# 1_LPC1850__P0-P4.net
KiCad netlist of a schematic drawn in Altium Designer
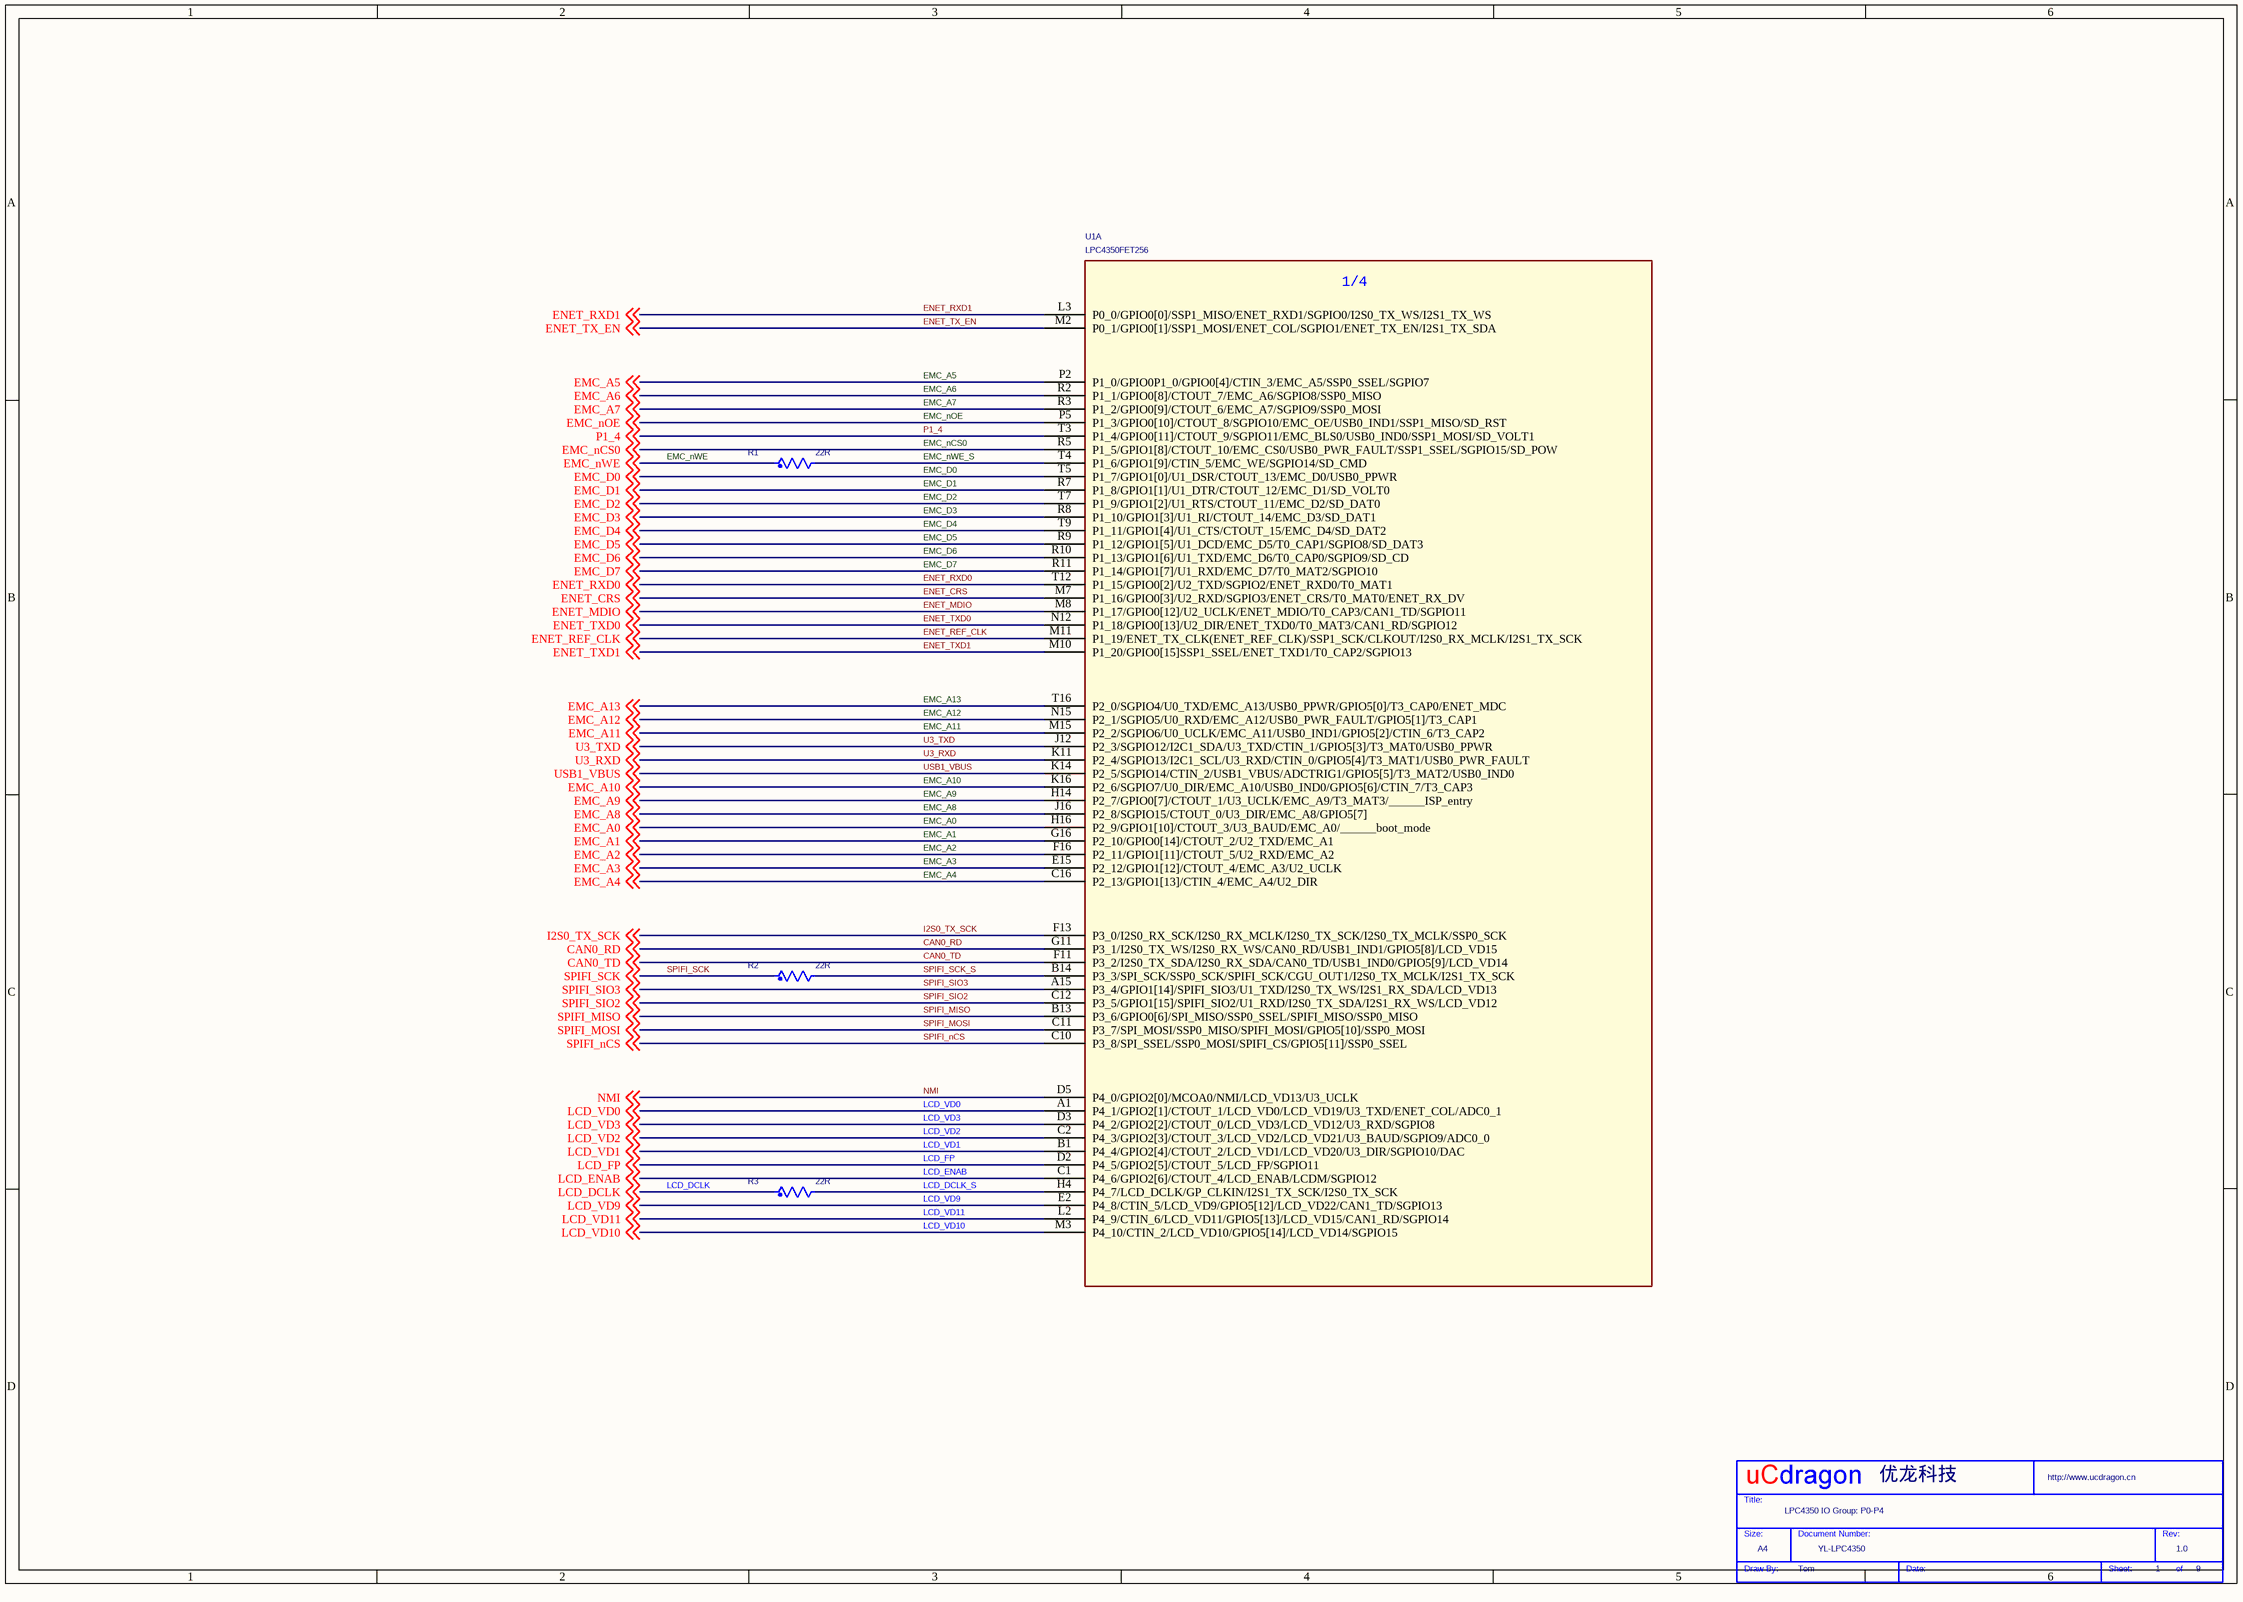
[diagram p0: 1) LPC1850_ P0-P4.SchDoc]

(export (version "E")
  (design (tool "Eeschema 10.0.6"))
  (components
    (comp (ref "*")
      (value "My Title 0")
      (fields
        (field (name "COMPANY") "优龙科技")
        (field (name "DRAWING") "Tom")
        (field (name "WEBSITE") "http://www.ucdragon.cn")
        (field (name "DOC") "YL-LPC4350")
        (field (name "REVCODE") "1.0")
        (field (name "TITLE") "LPC4350 IO Group: P0-P4")
        (field (name "PAGE SIZE") "A4")
        (field (name "PAGE NUMBER") "1")
        (field (name "PAGE COUNT") "9")
      )
      (libsource (lib "*") (part "My Title 0"))
    )
    (comp (ref "R1") (value "22R") (libsource (lib "*") (part "R_Generic_Dup2")))
    (comp (ref "R2") (value "22R") (libsource (lib "*") (part "R_Generic_Dup2")))
    (comp (ref "R3") (value "22R") (libsource (lib "*") (part "R_Generic_Dup2")))
    (comp (ref "U1")
      (value "LPC4350FET256")
      (footprint "LBGA256")
      (libsource (lib "*") (part "LPC4350FET256"))
    )
  )
  (nets
    (net (code "1") (name "/EMC_nWE_S") (class "Default")
      (node (ref "R1") (pin "2") (pinfunction "2_2") (pintype "passive"))
      (node (ref "U1") (pin "T4") (pinfunction "P1_6/GPIO1[9]/CTIN_5/EMC_WE/SGPIO14/SD_CMD_T4") (pintype "passive"))
    )
    (net (code "2") (name "/LCD_DCLK_S") (class "Default")
      (node (ref "R3") (pin "2") (pinfunction "2_2") (pintype "passive"))
      (node (ref "U1") (pin "H4") (pinfunction "P4_7/LCD_DCLK/GP_CLKIN/I2S1_TX_SCK/I2S0_TX_SCK_H4") (pintype "passive"))
    )
    (net (code "3") (name "/SPIFI_SCK_S") (class "Default")
      (node (ref "R2") (pin "2") (pinfunction "2_2") (pintype "passive"))
      (node (ref "U1") (pin "B14") (pinfunction "P3_3/SPI_SCK/SSP0_SCK/SPIFI_SCK/CGU_OUT1/I2S0_TX_MCLK/I2S1_TX_SCK_B14") (pintype "passive"))
    )
    (net (code "4") (name "CAN0_RD") (class "Default")
      (node (ref "U1") (pin "G11") (pinfunction "P3_1/I2S0_TX_WS/I2S0_RX_WS/CAN0_RD/USB1_IND1/GPIO5[8]/LCD_VD15_G11") (pintype "passive"))
    )
    (net (code "5") (name "CAN0_TD") (class "Default")
      (node (ref "U1") (pin "F11") (pinfunction "P3_2/I2S0_TX_SDA/I2S0_RX_SDA/CAN0_TD/USB1_IND0/GPIO5[9]/LCD_VD14_F11") (pintype "passive"))
    )
    (net (code "6") (name "EMC_A0") (class "Default")
      (node (ref "U1") (pin "H16") (pinfunction "P2_9/GPIO1[10]/CTOUT_3/U3_BAUD/EMC_A0/______boot_mode_H16") (pintype "passive"))
    )
    (net (code "7") (name "EMC_A1") (class "Default")
      (node (ref "U1") (pin "G16") (pinfunction "P2_10/GPIO0[14]/CTOUT_2/U2_TXD/EMC_A1_G16") (pintype "passive"))
    )
    (net (code "8") (name "EMC_A2") (class "Default")
      (node (ref "U1") (pin "F16") (pinfunction "P2_11/GPIO1[11]/CTOUT_5/U2_RXD/EMC_A2_F16") (pintype "passive"))
    )
    (net (code "9") (name "EMC_A3") (class "Default")
      (node (ref "U1") (pin "E15") (pinfunction "P2_12/GPIO1[12]/CTOUT_4/EMC_A3/U2_UCLK_E15") (pintype "passive"))
    )
    (net (code "10") (name "EMC_A4") (class "Default")
      (node (ref "U1") (pin "C16") (pinfunction "P2_13/GPIO1[13]/CTIN_4/EMC_A4/U2_DIR_C16") (pintype "passive"))
    )
    (net (code "11") (name "EMC_A5") (class "Default")
      (node (ref "U1") (pin "P2") (pinfunction "P1_0/GPIO0P1_0/GPIO0[4]/CTIN_3/EMC_A5/SSP0_SSEL/SGPIO7_P2") (pintype "passive"))
    )
    (net (code "12") (name "EMC_A6") (class "Default")
      (node (ref "U1") (pin "R2") (pinfunction "P1_1/GPIO0[8]/CTOUT_7/EMC_A6/SGPIO8/SSP0_MISO_R2") (pintype "passive"))
    )
    (net (code "13") (name "EMC_A7") (class "Default")
      (node (ref "U1") (pin "R3") (pinfunction "P1_2/GPIO0[9]/CTOUT_6/EMC_A7/SGPIO9/SSP0_MOSI_R3") (pintype "passive"))
    )
    (net (code "14") (name "EMC_A8") (class "Default")
      (node (ref "U1") (pin "J16") (pinfunction "P2_8/SGPIO15/CTOUT_0/U3_DIR/EMC_A8/GPIO5[7]_J16") (pintype "passive"))
    )
    (net (code "15") (name "EMC_A9") (class "Default")
      (node (ref "U1") (pin "H14") (pinfunction "P2_7/GPIO0[7]/CTOUT_1/U3_UCLK/EMC_A9/T3_MAT3/______ISP_entry_H14") (pintype "passive"))
    )
    (net (code "16") (name "EMC_A10") (class "Default")
      (node (ref "U1") (pin "K16") (pinfunction "P2_6/SGPIO7/U0_DIR/EMC_A10/USB0_IND0/GPIO5[6]/CTIN_7/T3_CAP3_K16") (pintype "passive"))
    )
    (net (code "17") (name "EMC_A11") (class "Default")
      (node (ref "U1") (pin "M15") (pinfunction "P2_2/SGPIO6/U0_UCLK/EMC_A11/USB0_IND1/GPIO5[2]/CTIN_6/T3_CAP2_M15") (pintype "passive"))
    )
    (net (code "18") (name "EMC_A12") (class "Default")
      (node (ref "U1") (pin "N15") (pinfunction "P2_1/SGPIO5/U0_RXD/EMC_A12/USB0_PWR_FAULT/GPIO5[1]/T3_CAP1_N15") (pintype "passive"))
    )
    (net (code "19") (name "EMC_A13") (class "Default")
      (node (ref "U1") (pin "T16") (pinfunction "P2_0/SGPIO4/U0_TXD/EMC_A13/USB0_PPWR/GPIO5[0]/T3_CAP0/ENET_MDC_T16") (pintype "passive"))
    )
    (net (code "20") (name "EMC_D0") (class "Default")
      (node (ref "U1") (pin "T5") (pinfunction "P1_7/GPIO1[0]/U1_DSR/CTOUT_13/EMC_D0/USB0_PPWR_T5") (pintype "passive"))
    )
    (net (code "21") (name "EMC_D1") (class "Default")
      (node (ref "U1") (pin "R7") (pinfunction "P1_8/GPIO1[1]/U1_DTR/CTOUT_12/EMC_D1/SD_VOLT0_R7") (pintype "passive"))
    )
    (net (code "22") (name "EMC_D2") (class "Default")
      (node (ref "U1") (pin "T7") (pinfunction "P1_9/GPIO1[2]/U1_RTS/CTOUT_11/EMC_D2/SD_DAT0_T7") (pintype "passive"))
    )
    (net (code "23") (name "EMC_D3") (class "Default")
      (node (ref "U1") (pin "R8") (pinfunction "P1_10/GPIO1[3]/U1_RI/CTOUT_14/EMC_D3/SD_DAT1_R8") (pintype "passive"))
    )
    (net (code "24") (name "EMC_D4") (class "Default")
      (node (ref "U1") (pin "T9") (pinfunction "P1_11/GPIO1[4]/U1_CTS/CTOUT_15/EMC_D4/SD_DAT2_T9") (pintype "passive"))
    )
    (net (code "25") (name "EMC_D5") (class "Default")
      (node (ref "U1") (pin "R9") (pinfunction "P1_12/GPIO1[5]/U1_DCD/EMC_D5/T0_CAP1/SGPIO8/SD_DAT3_R9") (pintype "passive"))
    )
    (net (code "26") (name "EMC_D6") (class "Default")
      (node (ref "U1") (pin "R10") (pinfunction "P1_13/GPIO1[6]/U1_TXD/EMC_D6/T0_CAP0/SGPIO9/SD_CD_R10") (pintype "passive"))
    )
    (net (code "27") (name "EMC_D7") (class "Default")
      (node (ref "U1") (pin "R11") (pinfunction "P1_14/GPIO1[7]/U1_RXD/EMC_D7/T0_MAT2/SGPIO10_R11") (pintype "passive"))
    )
    (net (code "28") (name "EMC_nCS0") (class "Default")
      (node (ref "U1") (pin "R5") (pinfunction "P1_5/GPIO1[8]/CTOUT_10/EMC_CS0/USB0_PWR_FAULT/SSP1_SSEL/SGPIO15/SD_POW_R5") (pintype "passive"))
    )
    (net (code "29") (name "EMC_nOE") (class "Default")
      (node (ref "U1") (pin "P5") (pinfunction "P1_3/GPIO0[10]/CTOUT_8/SGPIO10/EMC_OE/USB0_IND1/SSP1_MISO/SD_RST_P5") (pintype "passive"))
    )
    (net (code "30") (name "EMC_nWE") (class "Default")
      (node (ref "R1") (pin "1") (pinfunction "1_1") (pintype "passive"))
    )
    (net (code "31") (name "ENET_CRS") (class "Default")
      (node (ref "U1") (pin "M7") (pinfunction "P1_16/GPIO0[3]/U2_RXD/SGPIO3/ENET_CRS/T0_MAT0/ENET_RX_DV_M7") (pintype "passive"))
    )
    (net (code "32") (name "ENET_MDIO") (class "Default")
      (node (ref "U1") (pin "M8") (pinfunction "P1_17/GPIO0[12]/U2_UCLK/ENET_MDIO/T0_CAP3/CAN1_TD/SGPIO11_M8") (pintype "passive"))
    )
    (net (code "33") (name "ENET_REF_CLK") (class "Default")
      (node (ref "U1") (pin "M11") (pinfunction "P1_19/ENET_TX_CLK(ENET_REF_CLK)/SSP1_SCK/CLKOUT/I2S0_RX_MCLK/I2S1_TX_SCK_M11") (pintype "passive"))
    )
    (net (code "34") (name "ENET_RXD0") (class "Default")
      (node (ref "U1") (pin "T12") (pinfunction "P1_15/GPIO0[2]/U2_TXD/SGPIO2/ENET_RXD0/T0_MAT1_T12") (pintype "passive"))
    )
    (net (code "35") (name "ENET_RXD1") (class "Default")
      (node (ref "U1") (pin "L3") (pinfunction "P0_0/GPIO0[0]/SSP1_MISO/ENET_RXD1/SGPIO0/I2S0_TX_WS/I2S1_TX_WS_L3") (pintype "passive"))
    )
    (net (code "36") (name "ENET_TXD0") (class "Default")
      (node (ref "U1") (pin "N12") (pinfunction "P1_18/GPIO0[13]/U2_DIR/ENET_TXD0/T0_MAT3/CAN1_RD/SGPIO12_N12") (pintype "passive"))
    )
    (net (code "37") (name "ENET_TXD1") (class "Default")
      (node (ref "U1") (pin "M10") (pinfunction "P1_20/GPIO0[15]SSP1_SSEL/ENET_TXD1/T0_CAP2/SGPIO13_M10") (pintype "passive"))
    )
    (net (code "38") (name "ENET_TX_EN") (class "Default")
      (node (ref "U1") (pin "M2") (pinfunction "P0_1/GPIO0[1]/SSP1_MOSI/ENET_COL/SGPIO1/ENET_TX_EN/I2S1_TX_SDA_M2") (pintype "passive"))
    )
    (net (code "39") (name "I2S0_TX_SCK") (class "Default")
      (node (ref "U1") (pin "F13") (pinfunction "P3_0/I2S0_RX_SCK/I2S0_RX_MCLK/I2S0_TX_SCK/I2S0_TX_MCLK/SSP0_SCK_F13") (pintype "passive"))
    )
    (net (code "40") (name "LCD_DCLK") (class "Default")
      (node (ref "R3") (pin "1") (pinfunction "1_1") (pintype "passive"))
    )
    (net (code "41") (name "LCD_ENAB") (class "Default")
      (node (ref "U1") (pin "C1") (pinfunction "P4_6/GPIO2[6]/CTOUT_4/LCD_ENAB/LCDM/SGPIO12_C1") (pintype "passive"))
    )
    (net (code "42") (name "LCD_FP") (class "Default")
      (node (ref "U1") (pin "D2") (pinfunction "P4_5/GPIO2[5]/CTOUT_5/LCD_FP/SGPIO11_D2") (pintype "passive"))
    )
    (net (code "43") (name "LCD_VD0") (class "Default")
      (node (ref "U1") (pin "A1") (pinfunction "P4_1/GPIO2[1]/CTOUT_1/LCD_VD0/LCD_VD19/U3_TXD/ENET_COL/ADC0_1_A1") (pintype "passive"))
    )
    (net (code "44") (name "LCD_VD1") (class "Default")
      (node (ref "U1") (pin "B1") (pinfunction "P4_4/GPIO2[4]/CTOUT_2/LCD_VD1/LCD_VD20/U3_DIR/SGPIO10/DAC_B1") (pintype "passive"))
    )
    (net (code "45") (name "LCD_VD2") (class "Default")
      (node (ref "U1") (pin "C2") (pinfunction "P4_3/GPIO2[3]/CTOUT_3/LCD_VD2/LCD_VD21/U3_BAUD/SGPIO9/ADC0_0_C2") (pintype "passive"))
    )
    (net (code "46") (name "LCD_VD3") (class "Default")
      (node (ref "U1") (pin "D3") (pinfunction "P4_2/GPIO2[2]/CTOUT_0/LCD_VD3/LCD_VD12/U3_RXD/SGPIO8_D3") (pintype "passive"))
    )
    (net (code "47") (name "LCD_VD9") (class "Default")
      (node (ref "U1") (pin "E2") (pinfunction "P4_8/CTIN_5/LCD_VD9/GPIO5[12]/LCD_VD22/CAN1_TD/SGPIO13_E2") (pintype "passive"))
    )
    (net (code "48") (name "LCD_VD10") (class "Default")
      (node (ref "U1") (pin "M3") (pinfunction "P4_10/CTIN_2/LCD_VD10/GPIO5[14]/LCD_VD14/SGPIO15_M3") (pintype "passive"))
    )
    (net (code "49") (name "LCD_VD11") (class "Default")
      (node (ref "U1") (pin "L2") (pinfunction "P4_9/CTIN_6/LCD_VD11/GPIO5[13]/LCD_VD15/CAN1_RD/SGPIO14_L2") (pintype "passive"))
    )
    (net (code "50") (name "NMI") (class "Default")
      (node (ref "U1") (pin "D5") (pinfunction "P4_0/GPIO2[0]/MCOA0/NMI/LCD_VD13/U3_UCLK_D5") (pintype "passive"))
    )
    (net (code "51") (name "P1_4") (class "Default")
      (node (ref "U1") (pin "T3") (pinfunction "P1_4/GPIO0[11]/CTOUT_9/SGPIO11/EMC_BLS0/USB0_IND0/SSP1_MOSI/SD_VOLT1_T3") (pintype "passive"))
    )
    (net (code "52") (name "SPIFI_MISO") (class "Default")
      (node (ref "U1") (pin "B13") (pinfunction "P3_6/GPIO0[6]/SPI_MISO/SSP0_SSEL/SPIFI_MISO/SSP0_MISO_B13") (pintype "passive"))
    )
    (net (code "53") (name "SPIFI_MOSI") (class "Default")
      (node (ref "U1") (pin "C11") (pinfunction "P3_7/SPI_MOSI/SSP0_MISO/SPIFI_MOSI/GPIO5[10]/SSP0_MOSI_C11") (pintype "passive"))
    )
    (net (code "54") (name "SPIFI_SCK") (class "Default")
      (node (ref "R2") (pin "1") (pinfunction "1_1") (pintype "passive"))
    )
    (net (code "55") (name "SPIFI_SIO2") (class "Default")
      (node (ref "U1") (pin "C12") (pinfunction "P3_5/GPIO1[15]/SPIFI_SIO2/U1_RXD/I2S0_TX_SDA/I2S1_RX_WS/LCD_VD12_C12") (pintype "passive"))
    )
    (net (code "56") (name "SPIFI_SIO3") (class "Default")
      (node (ref "U1") (pin "A15") (pinfunction "P3_4/GPIO1[14]/SPIFI_SIO3/U1_TXD/I2S0_TX_WS/I2S1_RX_SDA/LCD_VD13_A15") (pintype "passive"))
    )
    (net (code "57") (name "SPIFI_nCS") (class "Default")
      (node (ref "U1") (pin "C10") (pinfunction "P3_8/SPI_SSEL/SSP0_MOSI/SPIFI_CS/GPIO5[11]/SSP0_SSEL_C10") (pintype "passive"))
    )
    (net (code "58") (name "U3_RXD") (class "Default")
      (node (ref "U1") (pin "K11") (pinfunction "P2_4/SGPIO13/I2C1_SCL/U3_RXD/CTIN_0/GPIO5[4]/T3_MAT1/USB0_PWR_FAULT_K11") (pintype "passive"))
    )
    (net (code "59") (name "U3_TXD") (class "Default")
      (node (ref "U1") (pin "J12") (pinfunction "P2_3/SGPIO12/I2C1_SDA/U3_TXD/CTIN_1/GPIO5[3]/T3_MAT0/USB0_PPWR_J12") (pintype "passive"))
    )
    (net (code "60") (name "USB1_VBUS") (class "Default")
      (node (ref "U1") (pin "K14") (pinfunction "P2_5/SGPIO14/CTIN_2/USB1_VBUS/ADCTRIG1/GPIO5[5]/T3_MAT2/USB0_IND0_K14") (pintype "passive"))
    )
  )
)
